# Board_Connector.net
KiCad netlist of a schematic drawn in Altium Designer
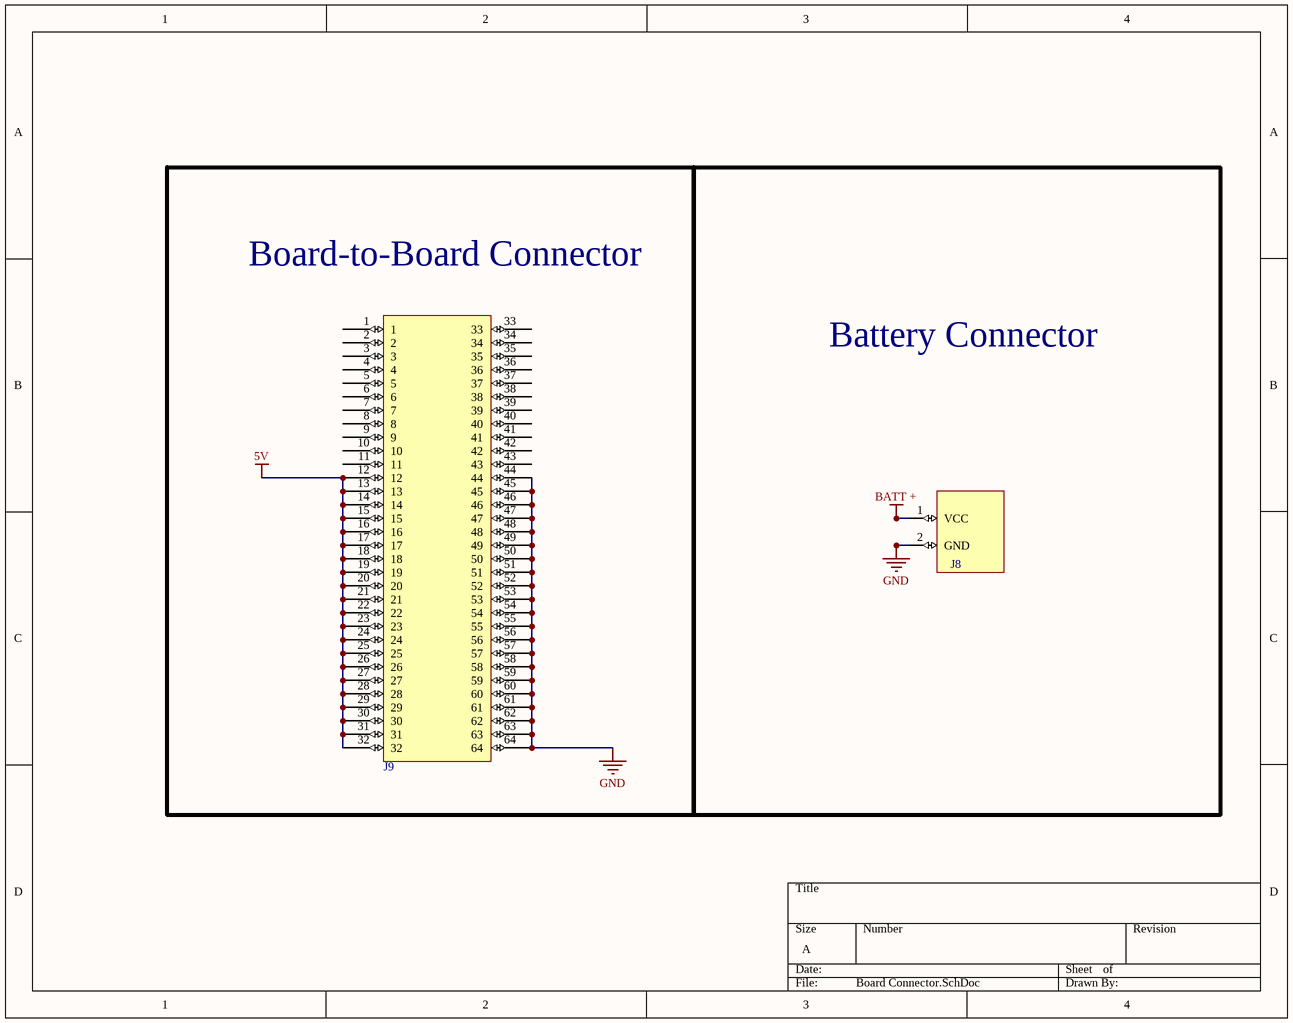
[diagram p0: Board Connector.SchDoc]

(export (version "E")
  (design (tool "Eeschema 10.0.6"))
  (components
    (comp (ref "J8")
      (value "Surface Mount Pad to solder battery connector wires from power bus bar")
      (footprint "Battery Connector")
      (description "Battery connector from bus bar to board")
      (libsource (lib "Connectors") (part "Battery Connector"))
    )
    (comp (ref "J9")
      (value "0714392464")
      (footprint "1.0mm mezzanine connector 64 pin")
      (description "64 Position Connector Receptacle, Outer Shroud Contacts Surface Mount Gold")
      (libsource (lib "Connectors") (part "0714392464"))
    )
  )
  (nets
    (net (code "1") (name "5V") (class "Default")
      (node (ref "J9") (pin "12") (pinfunction "12_12") (pintype "bidirectional"))
      (node (ref "J9") (pin "13") (pinfunction "13_13") (pintype "bidirectional"))
      (node (ref "J9") (pin "14") (pinfunction "14_14") (pintype "bidirectional"))
      (node (ref "J9") (pin "15") (pinfunction "15_15") (pintype "bidirectional"))
      (node (ref "J9") (pin "16") (pinfunction "16_16") (pintype "bidirectional"))
      (node (ref "J9") (pin "17") (pinfunction "17_17") (pintype "bidirectional"))
      (node (ref "J9") (pin "18") (pinfunction "18_18") (pintype "bidirectional"))
      (node (ref "J9") (pin "19") (pinfunction "19_19") (pintype "bidirectional"))
      (node (ref "J9") (pin "20") (pinfunction "20_20") (pintype "bidirectional"))
      (node (ref "J9") (pin "21") (pinfunction "21_21") (pintype "bidirectional"))
      (node (ref "J9") (pin "22") (pinfunction "22_22") (pintype "bidirectional"))
      (node (ref "J9") (pin "23") (pinfunction "23_23") (pintype "bidirectional"))
      (node (ref "J9") (pin "24") (pinfunction "24_24") (pintype "bidirectional"))
      (node (ref "J9") (pin "25") (pinfunction "25_25") (pintype "bidirectional"))
      (node (ref "J9") (pin "26") (pinfunction "26_26") (pintype "bidirectional"))
      (node (ref "J9") (pin "27") (pinfunction "27_27") (pintype "bidirectional"))
      (node (ref "J9") (pin "28") (pinfunction "28_28") (pintype "bidirectional"))
      (node (ref "J9") (pin "29") (pinfunction "29_29") (pintype "bidirectional"))
      (node (ref "J9") (pin "30") (pinfunction "30_30") (pintype "bidirectional"))
      (node (ref "J9") (pin "31") (pinfunction "31_31") (pintype "bidirectional"))
      (node (ref "J9") (pin "32") (pinfunction "32_32") (pintype "bidirectional"))
    )
    (net (code "2") (name "BATT +") (class "Default")
      (node (ref "J8") (pin "1") (pinfunction "VCC_1") (pintype "bidirectional"))
    )
    (net (code "3") (name "GND") (class "Default")
      (node (ref "J8") (pin "2") (pinfunction "GND_2") (pintype "bidirectional"))
      (node (ref "J9") (pin "44") (pinfunction "44_44") (pintype "bidirectional"))
      (node (ref "J9") (pin "45") (pinfunction "45_45") (pintype "bidirectional"))
      (node (ref "J9") (pin "46") (pinfunction "46_46") (pintype "bidirectional"))
      (node (ref "J9") (pin "47") (pinfunction "47_47") (pintype "bidirectional"))
      (node (ref "J9") (pin "48") (pinfunction "48_48") (pintype "bidirectional"))
      (node (ref "J9") (pin "49") (pinfunction "49_49") (pintype "bidirectional"))
      (node (ref "J9") (pin "50") (pinfunction "50_50") (pintype "bidirectional"))
      (node (ref "J9") (pin "51") (pinfunction "51_51") (pintype "bidirectional"))
      (node (ref "J9") (pin "52") (pinfunction "52_52") (pintype "bidirectional"))
      (node (ref "J9") (pin "53") (pinfunction "53_53") (pintype "bidirectional"))
      (node (ref "J9") (pin "54") (pinfunction "54_54") (pintype "bidirectional"))
      (node (ref "J9") (pin "55") (pinfunction "55_55") (pintype "bidirectional"))
      (node (ref "J9") (pin "56") (pinfunction "56_56") (pintype "bidirectional"))
      (node (ref "J9") (pin "57") (pinfunction "57_57") (pintype "bidirectional"))
      (node (ref "J9") (pin "58") (pinfunction "58_58") (pintype "bidirectional"))
      (node (ref "J9") (pin "59") (pinfunction "59_59") (pintype "bidirectional"))
      (node (ref "J9") (pin "60") (pinfunction "60_60") (pintype "bidirectional"))
      (node (ref "J9") (pin "61") (pinfunction "61_61") (pintype "bidirectional"))
      (node (ref "J9") (pin "62") (pinfunction "62_62") (pintype "bidirectional"))
      (node (ref "J9") (pin "63") (pinfunction "63_63") (pintype "bidirectional"))
      (node (ref "J9") (pin "64") (pinfunction "64_64") (pintype "bidirectional"))
    )
    (net (code "4") (name "unconnected-(J9-Pad1)") (class "Default")
      (node (ref "J9") (pin "1") (pinfunction "1_1") (pintype "bidirectional"))
    )
    (net (code "5") (name "unconnected-(J9-Pad2)") (class "Default")
      (node (ref "J9") (pin "2") (pinfunction "2_2") (pintype "bidirectional"))
    )
    (net (code "6") (name "unconnected-(J9-Pad3)") (class "Default")
      (node (ref "J9") (pin "3") (pinfunction "3_3") (pintype "bidirectional"))
    )
    (net (code "7") (name "unconnected-(J9-Pad4)") (class "Default")
      (node (ref "J9") (pin "4") (pinfunction "4_4") (pintype "bidirectional"))
    )
    (net (code "8") (name "unconnected-(J9-Pad5)") (class "Default")
      (node (ref "J9") (pin "5") (pinfunction "5_5") (pintype "bidirectional"))
    )
    (net (code "9") (name "unconnected-(J9-Pad6)") (class "Default")
      (node (ref "J9") (pin "6") (pinfunction "6_6") (pintype "bidirectional"))
    )
    (net (code "10") (name "unconnected-(J9-Pad7)") (class "Default")
      (node (ref "J9") (pin "7") (pinfunction "7_7") (pintype "bidirectional"))
    )
    (net (code "11") (name "unconnected-(J9-Pad8)") (class "Default")
      (node (ref "J9") (pin "8") (pinfunction "8_8") (pintype "bidirectional"))
    )
    (net (code "12") (name "unconnected-(J9-Pad9)") (class "Default")
      (node (ref "J9") (pin "9") (pinfunction "9_9") (pintype "bidirectional"))
    )
    (net (code "13") (name "unconnected-(J9-Pad10)") (class "Default")
      (node (ref "J9") (pin "10") (pinfunction "10_10") (pintype "bidirectional"))
    )
    (net (code "14") (name "unconnected-(J9-Pad11)") (class "Default")
      (node (ref "J9") (pin "11") (pinfunction "11_11") (pintype "bidirectional"))
    )
    (net (code "15") (name "unconnected-(J9-Pad33)") (class "Default")
      (node (ref "J9") (pin "33") (pinfunction "33_33") (pintype "bidirectional"))
    )
    (net (code "16") (name "unconnected-(J9-Pad34)") (class "Default")
      (node (ref "J9") (pin "34") (pinfunction "34_34") (pintype "bidirectional"))
    )
    (net (code "17") (name "unconnected-(J9-Pad35)") (class "Default")
      (node (ref "J9") (pin "35") (pinfunction "35_35") (pintype "bidirectional"))
    )
    (net (code "18") (name "unconnected-(J9-Pad36)") (class "Default")
      (node (ref "J9") (pin "36") (pinfunction "36_36") (pintype "bidirectional"))
    )
    (net (code "19") (name "unconnected-(J9-Pad37)") (class "Default")
      (node (ref "J9") (pin "37") (pinfunction "37_37") (pintype "bidirectional"))
    )
    (net (code "20") (name "unconnected-(J9-Pad38)") (class "Default")
      (node (ref "J9") (pin "38") (pinfunction "38_38") (pintype "bidirectional"))
    )
    (net (code "21") (name "unconnected-(J9-Pad39)") (class "Default")
      (node (ref "J9") (pin "39") (pinfunction "39_39") (pintype "bidirectional"))
    )
    (net (code "22") (name "unconnected-(J9-Pad40)") (class "Default")
      (node (ref "J9") (pin "40") (pinfunction "40_40") (pintype "bidirectional"))
    )
    (net (code "23") (name "unconnected-(J9-Pad41)") (class "Default")
      (node (ref "J9") (pin "41") (pinfunction "41_41") (pintype "bidirectional"))
    )
    (net (code "24") (name "unconnected-(J9-Pad42)") (class "Default")
      (node (ref "J9") (pin "42") (pinfunction "42_42") (pintype "bidirectional"))
    )
    (net (code "25") (name "unconnected-(J9-Pad43)") (class "Default")
      (node (ref "J9") (pin "43") (pinfunction "43_43") (pintype "bidirectional"))
    )
  )
)
